# DataControlBoard-Teensy.net
KiCad netlist of a schematic drawn in EAGLE
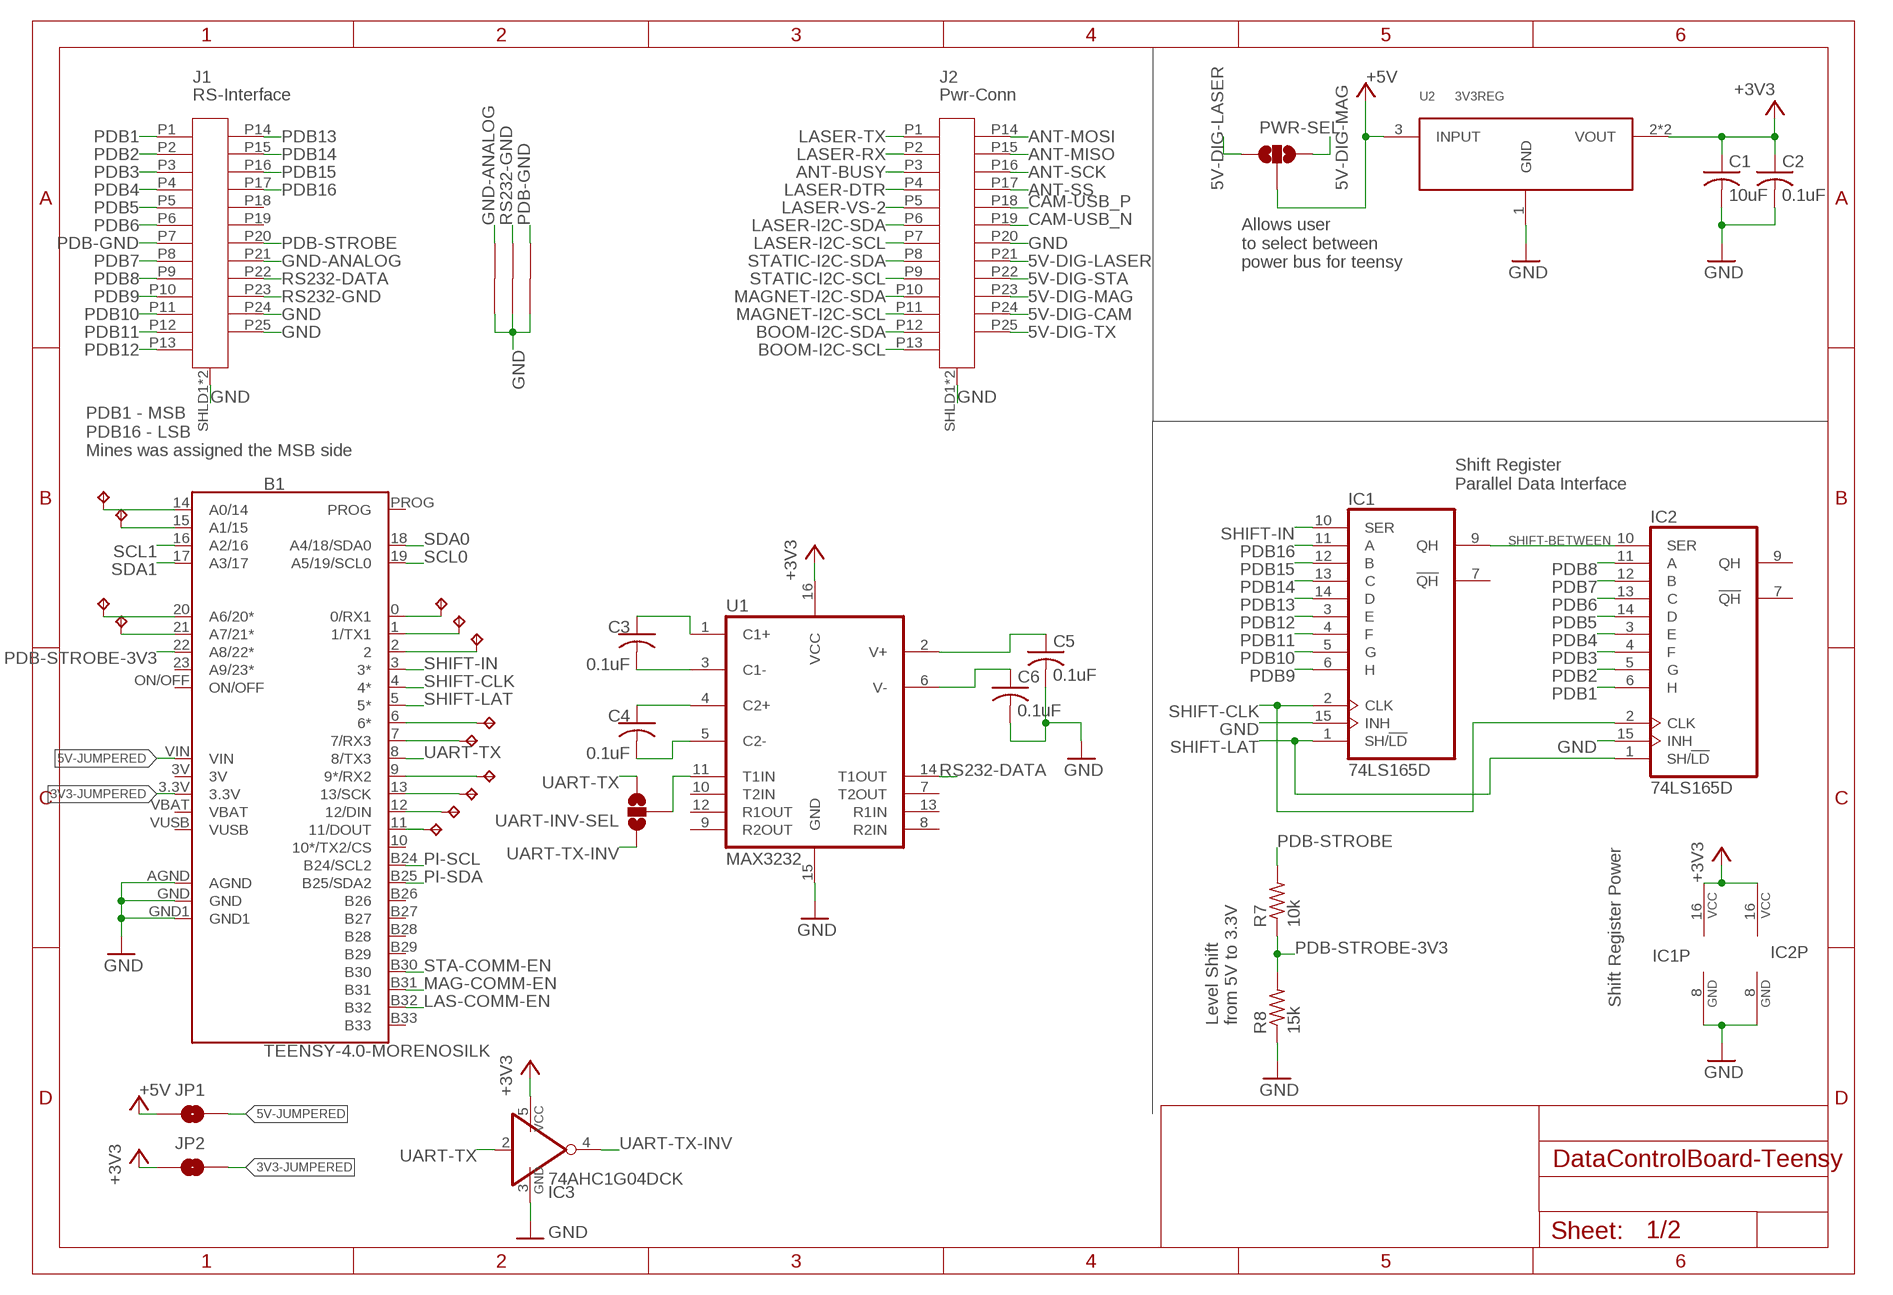
[diagram p0: schematic, sheet 1]
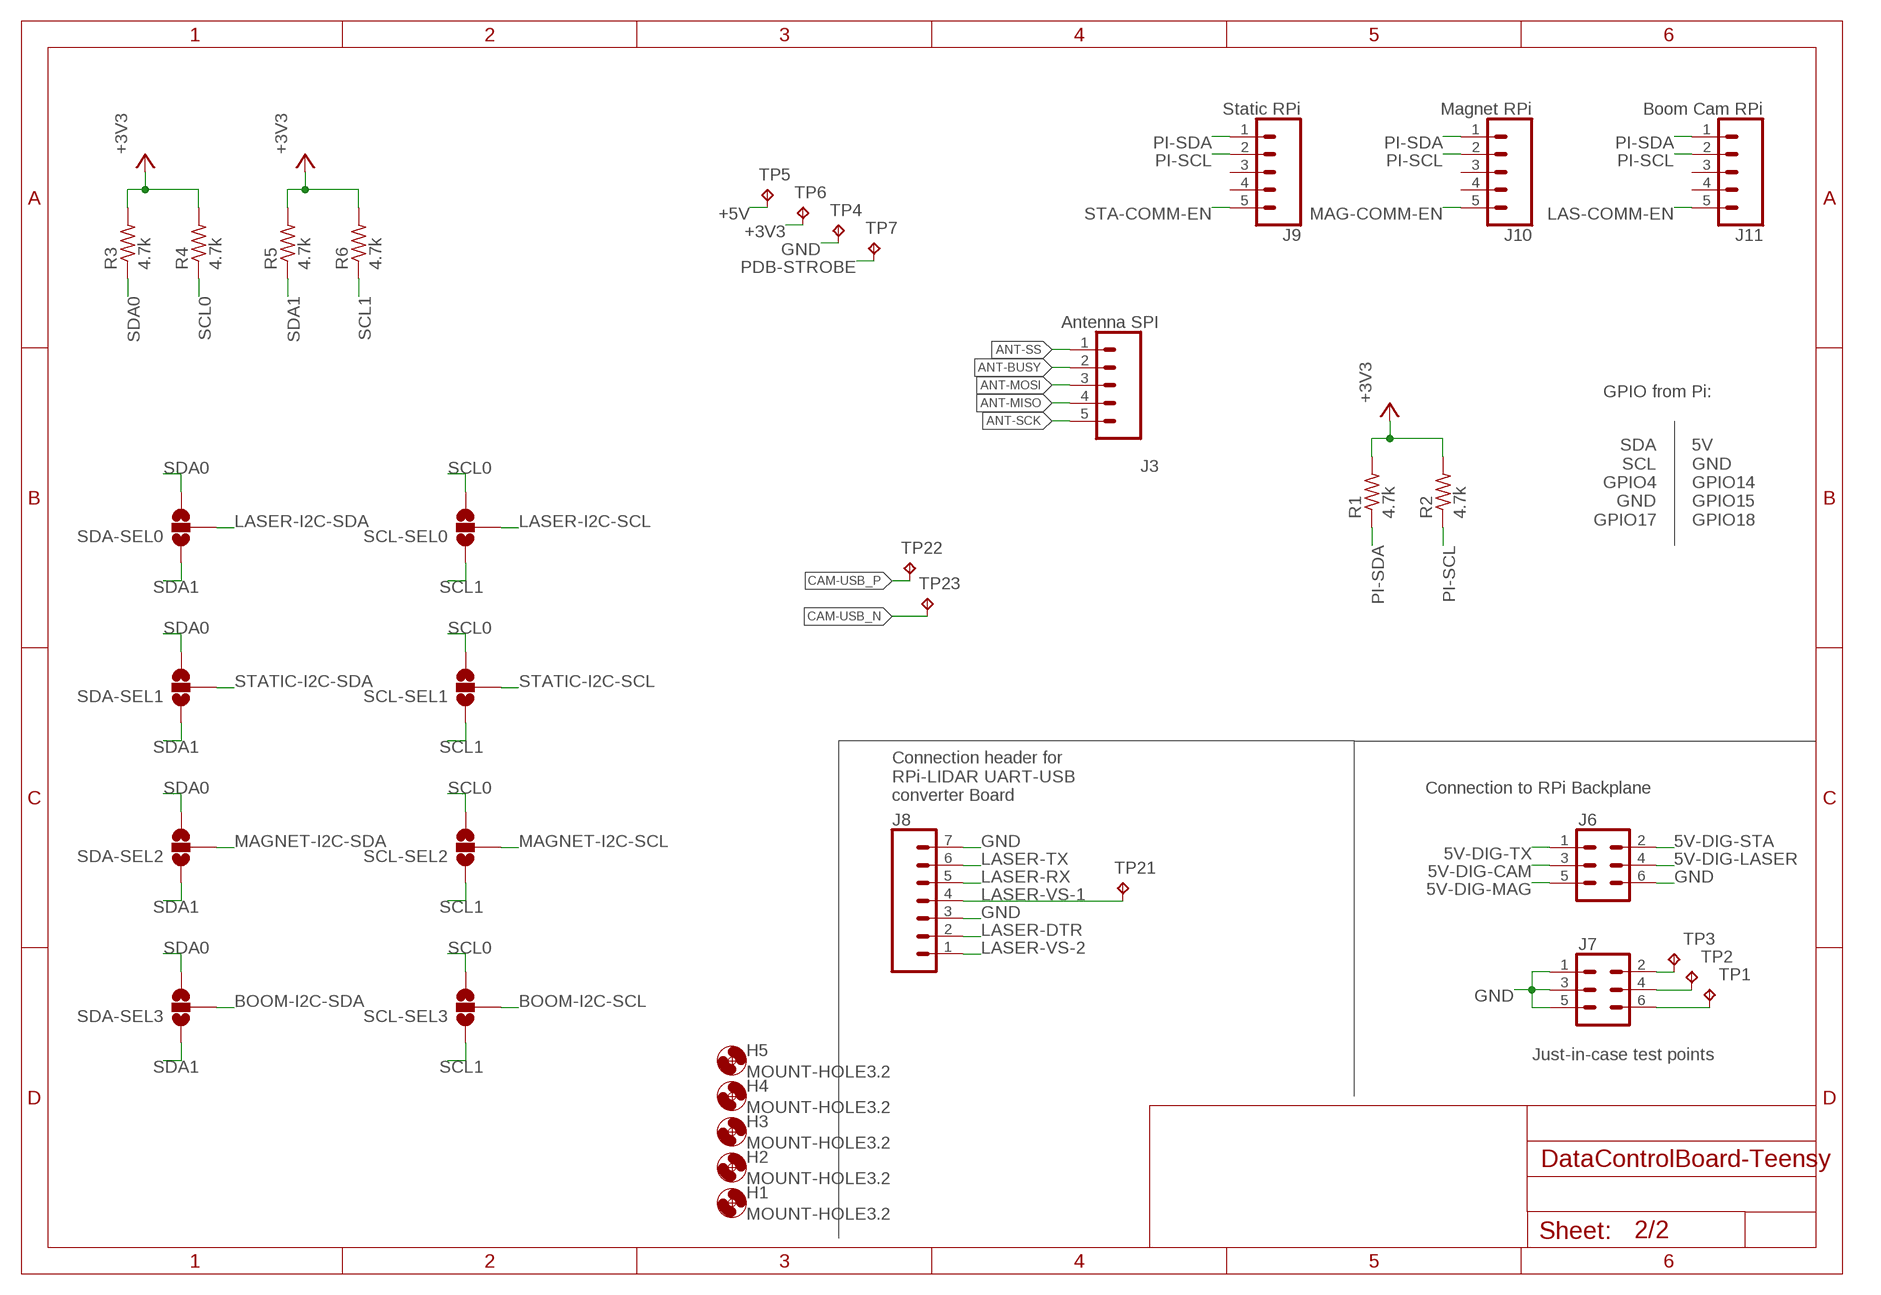
[diagram p1: schematic, sheet 2]

(export (version "E")
  (design (tool "Eeschema 10.0.6"))
  (components
    (comp (ref "B1")
      (value "TEENSY-4.0-MORENOSILK")
      (footprint "eagle-import:TEENSY-4.0_NOSILK")
      (libsource (lib "eagle-import") (part "TEENSY-4.0-MORENOSILK"))
    )
    (comp (ref "C1")
      (value "10uF")
      (footprint "eagle-import:C0805")
      (libsource (lib "eagle-import") (part "C-USC0805"))
    )
    (comp (ref "C2")
      (value "0.1uF")
      (footprint "eagle-import:C0805")
      (libsource (lib "eagle-import") (part "C-USC0805"))
    )
    (comp (ref "C3")
      (value "0.1uF")
      (footprint "eagle-import:C0805")
      (libsource (lib "eagle-import") (part "C-USC0805"))
    )
    (comp (ref "C4")
      (value "0.1uF")
      (footprint "eagle-import:C0805")
      (libsource (lib "eagle-import") (part "C-USC0805"))
    )
    (comp (ref "C5")
      (value "0.1uF")
      (footprint "eagle-import:C0805")
      (libsource (lib "eagle-import") (part "C-USC0805"))
    )
    (comp (ref "C6")
      (value "0.1uF")
      (footprint "eagle-import:C0805")
      (libsource (lib "eagle-import") (part "C-USC0805"))
    )
    (comp (ref "IC1")
      (value "74LS165D")
      (footprint "eagle-import:SO16")
      (libsource (lib "eagle-import") (part "74165DLS"))
    )
    (comp (ref "IC2")
      (value "74LS165D")
      (footprint "eagle-import:SO16")
      (libsource (lib "eagle-import") (part "74165DLS"))
    )
    (comp (ref "IC3")
      (value "74AHC1G04DCK")
      (footprint "eagle-import:SC70-5")
      (libsource (lib "eagle-import") (part "741G04DCKAHC"))
    )
    (comp (ref "J1")
      (value "RS-Interface")
      (footprint "eagle-import:MICRO-D25-RA")
      (libsource (lib "eagle-import") (part "MICRO-D25"))
    )
    (comp (ref "J2")
      (value "Pwr-Conn")
      (footprint "eagle-import:MICRO-D25-RA")
      (libsource (lib "eagle-import") (part "MICRO-D25"))
    )
    (comp (ref "JP1")
      (value "JUMPER-SMT_2_NO_NO-SILK")
      (footprint "eagle-import:SMT-JUMPER_2_NO_NO-SILK")
      (libsource (lib "eagle-import") (part "JUMPER-SMT_2_NO_NO-SILK"))
    )
    (comp (ref "JP2")
      (value "JUMPER-SMT_2_NO_NO-SILK")
      (footprint "eagle-import:SMT-JUMPER_2_NO_NO-SILK")
      (libsource (lib "eagle-import") (part "JUMPER-SMT_2_NO_NO-SILK"))
    )
    (comp (ref "PWR-SEL")
      (value "JUMPER-SMT_3_NO_NO-SILK")
      (footprint "eagle-import:SMT-JUMPER_3_NO_NO-SILK")
      (libsource (lib "eagle-import") (part "JUMPER-SMT_3_NO_NO-SILK"))
    )
    (comp (ref "R7")
      (value "10k")
      (footprint "eagle-import:R0805")
      (libsource (lib "eagle-import") (part "R-US_R0805"))
    )
    (comp (ref "R8")
      (value "15k")
      (footprint "eagle-import:R0805")
      (libsource (lib "eagle-import") (part "R-US_R0805"))
    )
    (comp (ref "TP8")
      (value "TPPAD1-13")
      (footprint "eagle-import:P1-13")
      (libsource (lib "eagle-import") (part "TPPAD1-13"))
    )
    (comp (ref "TP9")
      (value "TPPAD1-13")
      (footprint "eagle-import:P1-13")
      (libsource (lib "eagle-import") (part "TPPAD1-13"))
    )
    (comp (ref "TP10")
      (value "TPPAD1-13")
      (footprint "eagle-import:P1-13")
      (libsource (lib "eagle-import") (part "TPPAD1-13"))
    )
    (comp (ref "TP11")
      (value "TPPAD1-13")
      (footprint "eagle-import:P1-13")
      (libsource (lib "eagle-import") (part "TPPAD1-13"))
    )
    (comp (ref "TP12")
      (value "TPPAD1-13")
      (footprint "eagle-import:P1-13")
      (libsource (lib "eagle-import") (part "TPPAD1-13"))
    )
    (comp (ref "TP13")
      (value "TPPAD1-13")
      (footprint "eagle-import:P1-13")
      (libsource (lib "eagle-import") (part "TPPAD1-13"))
    )
    (comp (ref "TP14")
      (value "TPPAD1-13")
      (footprint "eagle-import:P1-13")
      (libsource (lib "eagle-import") (part "TPPAD1-13"))
    )
    (comp (ref "TP15")
      (value "TPPAD1-13")
      (footprint "eagle-import:P1-13")
      (libsource (lib "eagle-import") (part "TPPAD1-13"))
    )
    (comp (ref "TP16")
      (value "TPPAD1-13")
      (footprint "eagle-import:P1-13")
      (libsource (lib "eagle-import") (part "TPPAD1-13"))
    )
    (comp (ref "TP17")
      (value "TPPAD1-13")
      (footprint "eagle-import:P1-13")
      (libsource (lib "eagle-import") (part "TPPAD1-13"))
    )
    (comp (ref "TP18")
      (value "TPPAD1-13")
      (footprint "eagle-import:P1-13")
      (libsource (lib "eagle-import") (part "TPPAD1-13"))
    )
    (comp (ref "TP19")
      (value "TPPAD1-13")
      (footprint "eagle-import:P1-13")
      (libsource (lib "eagle-import") (part "TPPAD1-13"))
    )
    (comp (ref "TP20")
      (value "TPPAD1-13")
      (footprint "eagle-import:P1-13")
      (libsource (lib "eagle-import") (part "TPPAD1-13"))
    )
    (comp (ref "U$1")
      (value "GND-MERGER")
      (footprint "eagle-import:GND-MERGER")
      (libsource (lib "eagle-import") (part "GND-MERGER"))
    )
    (comp (ref "U$2")
      (value "GND-MERGER")
      (footprint "eagle-import:GND-MERGER")
      (libsource (lib "eagle-import") (part "GND-MERGER"))
    )
    (comp (ref "U$3")
      (value "GND-MERGER")
      (footprint "eagle-import:GND-MERGER")
      (libsource (lib "eagle-import") (part "GND-MERGER"))
    )
    (comp (ref "U1")
      (value "MAX3232")
      (footprint "eagle-import:SO16")
      (libsource (lib "eagle-import") (part "MAX2323SOIC16"))
    )
    (comp (ref "U2")
      (value "3V3REG")
      (footprint "eagle-import:SOT223")
      (libsource (lib "eagle-import") (part "3V3REG"))
    )
    (comp (ref "UART-INV-SEL")
      (value "JUMPER-SMT_3_NO_NO-SILK")
      (footprint "eagle-import:SMT-JUMPER_3_NO_NO-SILK")
      (libsource (lib "eagle-import") (part "JUMPER-SMT_3_NO_NO-SILK"))
    )
    (comp (ref "H1")
      (value "MOUNT-HOLE3.2")
      (footprint "eagle-import:3,2")
      (libsource (lib "eagle-import") (part "MOUNT-HOLE3.2"))
    )
    (comp (ref "H2")
      (value "MOUNT-HOLE3.2")
      (footprint "eagle-import:3,2")
      (libsource (lib "eagle-import") (part "MOUNT-HOLE3.2"))
    )
    (comp (ref "H3")
      (value "MOUNT-HOLE3.2")
      (footprint "eagle-import:3,2")
      (libsource (lib "eagle-import") (part "MOUNT-HOLE3.2"))
    )
    (comp (ref "H4")
      (value "MOUNT-HOLE3.2")
      (footprint "eagle-import:3,2")
      (libsource (lib "eagle-import") (part "MOUNT-HOLE3.2"))
    )
    (comp (ref "H5")
      (value "MOUNT-HOLE3.2")
      (footprint "eagle-import:3,2")
      (libsource (lib "eagle-import") (part "MOUNT-HOLE3.2"))
    )
    (comp (ref "J3")
      (value "Antenna SPI")
      (footprint "eagle-import:1X05_LOCK")
      (libsource (lib "eagle-import") (part "CONN_05LOCK"))
    )
    (comp (ref "J6")
      (value "CONN_03X22X3_SILK_MALE_PTH")
      (footprint "eagle-import:2X3")
      (libsource (lib "eagle-import") (part "CONN_03X22X3_SILK_MALE_PTH"))
    )
    (comp (ref "J7")
      (value "CONN_03X22X3_SILK_MALE_PTH")
      (footprint "eagle-import:2X3")
      (libsource (lib "eagle-import") (part "CONN_03X22X3_SILK_MALE_PTH"))
    )
    (comp (ref "J8")
      (value "CONN_07")
      (footprint "eagle-import:1X07")
      (libsource (lib "eagle-import") (part "CONN_07"))
    )
    (comp (ref "J9")
      (value "Static RPi")
      (footprint "eagle-import:1X05_LOCK")
      (libsource (lib "eagle-import") (part "CONN_05LOCK"))
    )
    (comp (ref "J10")
      (value "Magnet RPi")
      (footprint "eagle-import:1X05_LOCK")
      (libsource (lib "eagle-import") (part "CONN_05LOCK"))
    )
    (comp (ref "J11")
      (value "Boom Cam RPi")
      (footprint "eagle-import:1X05_LOCK")
      (libsource (lib "eagle-import") (part "CONN_05LOCK"))
    )
    (comp (ref "R1")
      (value "4.7k")
      (footprint "eagle-import:R0805")
      (libsource (lib "eagle-import") (part "R-US_R0805"))
    )
    (comp (ref "R2")
      (value "4.7k")
      (footprint "eagle-import:R0805")
      (libsource (lib "eagle-import") (part "R-US_R0805"))
    )
    (comp (ref "R3")
      (value "4.7k")
      (footprint "eagle-import:R0805")
      (libsource (lib "eagle-import") (part "R-US_R0805"))
    )
    (comp (ref "R4")
      (value "4.7k")
      (footprint "eagle-import:R0805")
      (libsource (lib "eagle-import") (part "R-US_R0805"))
    )
    (comp (ref "R5")
      (value "4.7k")
      (footprint "eagle-import:R0805")
      (libsource (lib "eagle-import") (part "R-US_R0805"))
    )
    (comp (ref "R6")
      (value "4.7k")
      (footprint "eagle-import:R0805")
      (libsource (lib "eagle-import") (part "R-US_R0805"))
    )
    (comp (ref "SCL-SEL0")
      (value "JUMPER-SMT_3_NO_NO-SILK")
      (footprint "eagle-import:SMT-JUMPER_3_NO_NO-SILK")
      (libsource (lib "eagle-import") (part "JUMPER-SMT_3_NO_NO-SILK"))
    )
    (comp (ref "SCL-SEL1")
      (value "JUMPER-SMT_3_NO_NO-SILK")
      (footprint "eagle-import:SMT-JUMPER_3_NO_NO-SILK")
      (libsource (lib "eagle-import") (part "JUMPER-SMT_3_NO_NO-SILK"))
    )
    (comp (ref "SCL-SEL2")
      (value "JUMPER-SMT_3_NO_NO-SILK")
      (footprint "eagle-import:SMT-JUMPER_3_NO_NO-SILK")
      (libsource (lib "eagle-import") (part "JUMPER-SMT_3_NO_NO-SILK"))
    )
    (comp (ref "SCL-SEL3")
      (value "JUMPER-SMT_3_NO_NO-SILK")
      (footprint "eagle-import:SMT-JUMPER_3_NO_NO-SILK")
      (libsource (lib "eagle-import") (part "JUMPER-SMT_3_NO_NO-SILK"))
    )
    (comp (ref "SDA-SEL0")
      (value "JUMPER-SMT_3_NO_NO-SILK")
      (footprint "eagle-import:SMT-JUMPER_3_NO_NO-SILK")
      (libsource (lib "eagle-import") (part "JUMPER-SMT_3_NO_NO-SILK"))
    )
    (comp (ref "SDA-SEL1")
      (value "JUMPER-SMT_3_NO_NO-SILK")
      (footprint "eagle-import:SMT-JUMPER_3_NO_NO-SILK")
      (libsource (lib "eagle-import") (part "JUMPER-SMT_3_NO_NO-SILK"))
    )
    (comp (ref "SDA-SEL2")
      (value "JUMPER-SMT_3_NO_NO-SILK")
      (footprint "eagle-import:SMT-JUMPER_3_NO_NO-SILK")
      (libsource (lib "eagle-import") (part "JUMPER-SMT_3_NO_NO-SILK"))
    )
    (comp (ref "SDA-SEL3")
      (value "JUMPER-SMT_3_NO_NO-SILK")
      (footprint "eagle-import:SMT-JUMPER_3_NO_NO-SILK")
      (libsource (lib "eagle-import") (part "JUMPER-SMT_3_NO_NO-SILK"))
    )
    (comp (ref "TP1")
      (value "TPPAD1-13")
      (footprint "eagle-import:P1-13")
      (libsource (lib "eagle-import") (part "TPPAD1-13"))
    )
    (comp (ref "TP2")
      (value "TPPAD1-13")
      (footprint "eagle-import:P1-13")
      (libsource (lib "eagle-import") (part "TPPAD1-13"))
    )
    (comp (ref "TP3")
      (value "TPPAD1-13")
      (footprint "eagle-import:P1-13")
      (libsource (lib "eagle-import") (part "TPPAD1-13"))
    )
    (comp (ref "TP4")
      (value "GND")
      (footprint "eagle-import:P1-13")
      (libsource (lib "eagle-import") (part "TPPAD1-13"))
    )
    (comp (ref "TP5")
      (value "5V")
      (footprint "eagle-import:P1-13")
      (libsource (lib "eagle-import") (part "TPPAD1-13"))
    )
    (comp (ref "TP6")
      (value "3.3V")
      (footprint "eagle-import:P1-13")
      (libsource (lib "eagle-import") (part "TPPAD1-13"))
    )
    (comp (ref "TP7")
      (value "STROBE")
      (footprint "eagle-import:P1-13")
      (libsource (lib "eagle-import") (part "TPPAD1-13"))
    )
    (comp (ref "TP21")
      (value "TPPAD1-13")
      (footprint "eagle-import:P1-13")
      (libsource (lib "eagle-import") (part "TPPAD1-13"))
    )
    (comp (ref "TP22")
      (value "TPPAD1-13")
      (footprint "eagle-import:P1-13")
      (libsource (lib "eagle-import") (part "TPPAD1-13"))
    )
    (comp (ref "TP23")
      (value "TPPAD1-13")
      (footprint "eagle-import:P1-13")
      (libsource (lib "eagle-import") (part "TPPAD1-13"))
    )
  )
  (nets
    (net (code "1") (name "+3V3") (class "Default")
      (node (ref "C1") (pin "1") (pinfunction "1_1") (pintype "passive"))
      (node (ref "C2") (pin "1") (pinfunction "1_1") (pintype "passive"))
      (node (ref "IC1") (pin "16") (pinfunction "VCC_16") (pintype "power_in"))
      (node (ref "IC2") (pin "16") (pinfunction "VCC_16") (pintype "power_in"))
      (node (ref "IC3") (pin "5") (pinfunction "VCC_5") (pintype "power_in"))
      (node (ref "JP2") (pin "1") (pinfunction "1_1") (pintype "passive"))
      (node (ref "R1") (pin "2") (pinfunction "2_2") (pintype "passive"))
      (node (ref "R2") (pin "2") (pinfunction "2_2") (pintype "passive"))
      (node (ref "R3") (pin "2") (pinfunction "2_2") (pintype "passive"))
      (node (ref "R4") (pin "2") (pinfunction "2_2") (pintype "passive"))
      (node (ref "R5") (pin "2") (pinfunction "2_2") (pintype "passive"))
      (node (ref "R6") (pin "2") (pinfunction "2_2") (pintype "passive"))
      (node (ref "TP6") (pin "TP") (pinfunction "TP_TP") (pintype "input"))
      (node (ref "U1") (pin "16") (pinfunction "VCC_16") (pintype "bidirectional"))
      (node (ref "U2") (pin "2") (pinfunction "VOUT_2") (pintype "bidirectional"))
      (node (ref "U2") (pin "4") (pinfunction "VOUT_4") (pintype "bidirectional"))
    )
    (net (code "2") (name "+5V") (class "Default")
      (node (ref "JP1") (pin "1") (pinfunction "1_1") (pintype "passive"))
      (node (ref "PWR-SEL") (pin "2") (pinfunction "2_2") (pintype "passive"))
      (node (ref "TP5") (pin "TP") (pinfunction "TP_TP") (pintype "input"))
      (node (ref "U2") (pin "3") (pinfunction "INPUT_3") (pintype "bidirectional"))
    )
    (net (code "3") (name "3V") (class "Default")
      (node (ref "B1") (pin "3V") (pinfunction "3V_3V") (pintype "power_in"))
    )
    (net (code "4") (name "3V3-JUMPERED") (class "Default")
      (node (ref "B1") (pin "3.3V") (pinfunction "3.3V_3.3V") (pintype "power_in"))
      (node (ref "JP2") (pin "2") (pinfunction "2_2") (pintype "passive"))
    )
    (net (code "5") (name "5V-DIG-CAM") (class "Default")
      (node (ref "J2") (pin "P24") (pinfunction "P24_P24") (pintype "bidirectional"))
      (node (ref "J6") (pin "3") (pinfunction "3_3") (pintype "bidirectional"))
    )
    (net (code "6") (name "5V-DIG-LASER") (class "Default")
      (node (ref "J2") (pin "P21") (pinfunction "P21_P21") (pintype "bidirectional"))
      (node (ref "J6") (pin "4") (pinfunction "4_4") (pintype "bidirectional"))
      (node (ref "PWR-SEL") (pin "1") (pinfunction "1_1") (pintype "passive"))
    )
    (net (code "7") (name "5V-DIG-MAG") (class "Default")
      (node (ref "J2") (pin "P23") (pinfunction "P23_P23") (pintype "bidirectional"))
      (node (ref "J6") (pin "5") (pinfunction "5_5") (pintype "bidirectional"))
      (node (ref "PWR-SEL") (pin "3") (pinfunction "3_3") (pintype "passive"))
    )
    (net (code "8") (name "5V-DIG-STA") (class "Default")
      (node (ref "J2") (pin "P22") (pinfunction "P22_P22") (pintype "bidirectional"))
      (node (ref "J6") (pin "2") (pinfunction "2_2") (pintype "bidirectional"))
    )
    (net (code "9") (name "5V-DIG-TX") (class "Default")
      (node (ref "J2") (pin "P25") (pinfunction "P25_P25") (pintype "bidirectional"))
      (node (ref "J6") (pin "1") (pinfunction "1_1") (pintype "bidirectional"))
    )
    (net (code "10") (name "5V-JUMPERED") (class "Default")
      (node (ref "B1") (pin "VIN") (pinfunction "VIN_VIN") (pintype "power_in"))
      (node (ref "JP1") (pin "2") (pinfunction "2_2") (pintype "passive"))
    )
    (net (code "11") (name "ANT-BUSY") (class "Default")
      (node (ref "J2") (pin "P3") (pinfunction "P3_P3") (pintype "bidirectional"))
      (node (ref "J3") (pin "2") (pinfunction "2_2") (pintype "passive"))
    )
    (net (code "12") (name "ANT-MISO") (class "Default")
      (node (ref "J2") (pin "P15") (pinfunction "P15_P15") (pintype "bidirectional"))
      (node (ref "J3") (pin "4") (pinfunction "4_4") (pintype "passive"))
    )
    (net (code "13") (name "ANT-MOSI") (class "Default")
      (node (ref "J2") (pin "P14") (pinfunction "P14_P14") (pintype "bidirectional"))
      (node (ref "J3") (pin "3") (pinfunction "3_3") (pintype "passive"))
    )
    (net (code "14") (name "ANT-SCK") (class "Default")
      (node (ref "J2") (pin "P16") (pinfunction "P16_P16") (pintype "bidirectional"))
      (node (ref "J3") (pin "5") (pinfunction "5_5") (pintype "passive"))
    )
    (net (code "15") (name "ANT-SS") (class "Default")
      (node (ref "J2") (pin "P17") (pinfunction "P17_P17") (pintype "bidirectional"))
      (node (ref "J3") (pin "1") (pinfunction "1_1") (pintype "passive"))
    )
    (net (code "16") (name "BOOM-I2C-SCL") (class "Default")
      (node (ref "J2") (pin "P13") (pinfunction "P13_P13") (pintype "bidirectional"))
      (node (ref "SCL-SEL3") (pin "2") (pinfunction "2_2") (pintype "passive"))
    )
    (net (code "17") (name "BOOM-I2C-SDA") (class "Default")
      (node (ref "J2") (pin "P12") (pinfunction "P12_P12") (pintype "bidirectional"))
      (node (ref "SDA-SEL3") (pin "2") (pinfunction "2_2") (pintype "passive"))
    )
    (net (code "18") (name "CAM-USB_N") (class "Default")
      (node (ref "J2") (pin "P19") (pinfunction "P19_P19") (pintype "bidirectional"))
      (node (ref "TP23") (pin "TP") (pinfunction "TP_TP") (pintype "input"))
    )
    (net (code "19") (name "CAM-USB_P") (class "Default")
      (node (ref "J2") (pin "P18") (pinfunction "P18_P18") (pintype "bidirectional"))
      (node (ref "TP22") (pin "TP") (pinfunction "TP_TP") (pintype "input"))
    )
    (net (code "20") (name "GND") (class "Default")
      (node (ref "B1") (pin "AGND") (pinfunction "AGND_AGND") (pintype "power_in"))
      (node (ref "B1") (pin "GND") (pinfunction "GND_GND") (pintype "power_in"))
      (node (ref "B1") (pin "GND1") (pinfunction "GND1_GND1") (pintype "power_in"))
      (node (ref "C1") (pin "2") (pinfunction "2_2") (pintype "passive"))
      (node (ref "C2") (pin "2") (pinfunction "2_2") (pintype "passive"))
      (node (ref "C5") (pin "2") (pinfunction "2_2") (pintype "passive"))
      (node (ref "C6") (pin "2") (pinfunction "2_2") (pintype "passive"))
      (node (ref "IC1") (pin "15") (pinfunction "INH_15") (pintype "input"))
      (node (ref "IC1") (pin "8") (pinfunction "GND_8") (pintype "power_in"))
      (node (ref "IC2") (pin "15") (pinfunction "INH_15") (pintype "input"))
      (node (ref "IC2") (pin "8") (pinfunction "GND_8") (pintype "power_in"))
      (node (ref "IC3") (pin "3") (pinfunction "GND_3") (pintype "power_in"))
      (node (ref "J1") (pin "P24") (pinfunction "P24_P24") (pintype "bidirectional"))
      (node (ref "J1") (pin "P25") (pinfunction "P25_P25") (pintype "bidirectional"))
      (node (ref "J1") (pin "SHLD1") (pinfunction "SHLD_SHLD1") (pintype "bidirectional"))
      (node (ref "J1") (pin "SHLD2") (pinfunction "SHLD_SHLD2") (pintype "bidirectional"))
      (node (ref "J2") (pin "P20") (pinfunction "P20_P20") (pintype "bidirectional"))
      (node (ref "J2") (pin "SHLD1") (pinfunction "SHLD_SHLD1") (pintype "bidirectional"))
      (node (ref "J2") (pin "SHLD2") (pinfunction "SHLD_SHLD2") (pintype "bidirectional"))
      (node (ref "J6") (pin "6") (pinfunction "6_6") (pintype "bidirectional"))
      (node (ref "J7") (pin "1") (pinfunction "1_1") (pintype "bidirectional"))
      (node (ref "J7") (pin "3") (pinfunction "3_3") (pintype "bidirectional"))
      (node (ref "J7") (pin "5") (pinfunction "5_5") (pintype "bidirectional"))
      (node (ref "J8") (pin "3") (pinfunction "3_3") (pintype "passive"))
      (node (ref "J8") (pin "7") (pinfunction "7_7") (pintype "passive"))
      (node (ref "R8") (pin "1") (pinfunction "1_1") (pintype "passive"))
      (node (ref "TP4") (pin "TP") (pinfunction "TP_TP") (pintype "input"))
      (node (ref "U$1") (pin "P$1") (pinfunction "P$1_P$1") (pintype "bidirectional"))
      (node (ref "U$2") (pin "P$1") (pinfunction "P$1_P$1") (pintype "bidirectional"))
      (node (ref "U$3") (pin "P$1") (pinfunction "P$1_P$1") (pintype "bidirectional"))
      (node (ref "U1") (pin "15") (pinfunction "GND_15") (pintype "bidirectional"))
      (node (ref "U2") (pin "1") (pinfunction "GND_1") (pintype "bidirectional"))
    )
    (net (code "21") (name "GND-ANALOG") (class "Default")
      (node (ref "J1") (pin "P21") (pinfunction "P21_P21") (pintype "bidirectional"))
      (node (ref "U$1") (pin "P$2") (pinfunction "P$2_P$2") (pintype "bidirectional"))
    )
    (net (code "22") (name "LAS-COMM-EN") (class "Default")
      (node (ref "B1") (pin "B32") (pinfunction "B32_B32") (pintype "bidirectional"))
      (node (ref "J11") (pin "5") (pinfunction "5_5") (pintype "passive"))
    )
    (net (code "23") (name "LASER-DTR") (class "Default")
      (node (ref "J2") (pin "P4") (pinfunction "P4_P4") (pintype "bidirectional"))
      (node (ref "J8") (pin "2") (pinfunction "2_2") (pintype "passive"))
    )
    (net (code "24") (name "LASER-I2C-SCL") (class "Default")
      (node (ref "J2") (pin "P7") (pinfunction "P7_P7") (pintype "bidirectional"))
      (node (ref "SCL-SEL0") (pin "2") (pinfunction "2_2") (pintype "passive"))
    )
    (net (code "25") (name "LASER-I2C-SDA") (class "Default")
      (node (ref "J2") (pin "P6") (pinfunction "P6_P6") (pintype "bidirectional"))
      (node (ref "SDA-SEL0") (pin "2") (pinfunction "2_2") (pintype "passive"))
    )
    (net (code "26") (name "LASER-RX") (class "Default")
      (node (ref "J2") (pin "P2") (pinfunction "P2_P2") (pintype "bidirectional"))
      (node (ref "J8") (pin "5") (pinfunction "5_5") (pintype "passive"))
    )
    (net (code "27") (name "LASER-TX") (class "Default")
      (node (ref "J2") (pin "P1") (pinfunction "P1_P1") (pintype "bidirectional"))
      (node (ref "J8") (pin "6") (pinfunction "6_6") (pintype "passive"))
    )
    (net (code "28") (name "LASER-VS-1") (class "Default")
      (node (ref "J8") (pin "4") (pinfunction "4_4") (pintype "passive"))
      (node (ref "TP21") (pin "TP") (pinfunction "TP_TP") (pintype "input"))
    )
    (net (code "29") (name "LASER-VS-2") (class "Default")
      (node (ref "J2") (pin "P5") (pinfunction "P5_P5") (pintype "bidirectional"))
      (node (ref "J8") (pin "1") (pinfunction "1_1") (pintype "passive"))
    )
    (net (code "30") (name "MAG-COMM-EN") (class "Default")
      (node (ref "B1") (pin "B31") (pinfunction "B31_B31") (pintype "bidirectional"))
      (node (ref "J10") (pin "5") (pinfunction "5_5") (pintype "passive"))
    )
    (net (code "31") (name "MAGNET-I2C-SCL") (class "Default")
      (node (ref "J2") (pin "P11") (pinfunction "P11_P11") (pintype "bidirectional"))
      (node (ref "SCL-SEL2") (pin "2") (pinfunction "2_2") (pintype "passive"))
    )
    (net (code "32") (name "MAGNET-I2C-SDA") (class "Default")
      (node (ref "J2") (pin "P10") (pinfunction "P10_P10") (pintype "bidirectional"))
      (node (ref "SDA-SEL2") (pin "2") (pinfunction "2_2") (pintype "passive"))
    )
    (net (code "33") (name "Net-(B1-0{slash}RX1)") (class "Default")
      (node (ref "B1") (pin "0") (pinfunction "0/RX1_0") (pintype "bidirectional"))
      (node (ref "TP12") (pin "TP") (pinfunction "TP_TP") (pintype "input"))
    )
    (net (code "34") (name "Net-(B1-1{slash}TX1)") (class "Default")
      (node (ref "B1") (pin "1") (pinfunction "1/TX1_1") (pintype "bidirectional"))
      (node (ref "TP13") (pin "TP") (pinfunction "TP_TP") (pintype "input"))
    )
    (net (code "35") (name "Net-(B1-6*)") (class "Default")
      (node (ref "B1") (pin "6") (pinfunction "6*_6") (pintype "bidirectional"))
      (node (ref "TP19") (pin "TP") (pinfunction "TP_TP") (pintype "input"))
    )
    (net (code "36") (name "Net-(B1-7{slash}RX3)") (class "Default")
      (node (ref "B1") (pin "7") (pinfunction "7/RX3_7") (pintype "bidirectional"))
      (node (ref "TP20") (pin "TP") (pinfunction "TP_TP") (pintype "input"))
    )
    (net (code "37") (name "Net-(B1-9*{slash}RX2)") (class "Default")
      (node (ref "B1") (pin "9") (pinfunction "9*/RX2_9") (pintype "bidirectional"))
      (node (ref "TP15") (pin "TP") (pinfunction "TP_TP") (pintype "input"))
    )
    (net (code "38") (name "Net-(B1-11{slash}DOUT)") (class "Default")
      (node (ref "B1") (pin "11") (pinfunction "11/DOUT_11") (pintype "bidirectional"))
      (node (ref "TP18") (pin "TP") (pinfunction "TP_TP") (pintype "input"))
    )
    (net (code "39") (name "Net-(B1-12{slash}DIN)") (class "Default")
      (node (ref "B1") (pin "12") (pinfunction "12/DIN_12") (pintype "bidirectional"))
      (node (ref "TP17") (pin "TP") (pinfunction "TP_TP") (pintype "input"))
    )
    (net (code "40") (name "Net-(B1-13{slash}SCK)") (class "Default")
      (node (ref "B1") (pin "13") (pinfunction "13/SCK_13") (pintype "bidirectional"))
      (node (ref "TP16") (pin "TP") (pinfunction "TP_TP") (pintype "input"))
    )
    (net (code "41") (name "Net-(B1-A0{slash}14)") (class "Default")
      (node (ref "B1") (pin "14") (pinfunction "A0/14_14") (pintype "bidirectional"))
      (node (ref "TP8") (pin "TP") (pinfunction "TP_TP") (pintype "input"))
    )
    (net (code "42") (name "Net-(B1-A1{slash}15)") (class "Default")
      (node (ref "B1") (pin "15") (pinfunction "A1/15_15") (pintype "bidirectional"))
      (node (ref "TP9") (pin "TP") (pinfunction "TP_TP") (pintype "input"))
    )
    (net (code "43") (name "Net-(B1-A6{slash}20*)") (class "Default")
      (node (ref "B1") (pin "20") (pinfunction "A6/20*_20") (pintype "bidirectional"))
      (node (ref "TP10") (pin "TP") (pinfunction "TP_TP") (pintype "input"))
    )
    (net (code "44") (name "Net-(B1-A7{slash}21*)") (class "Default")
      (node (ref "B1") (pin "21") (pinfunction "A7/21*_21") (pintype "bidirectional"))
      (node (ref "TP11") (pin "TP") (pinfunction "TP_TP") (pintype "input"))
    )
    (net (code "45") (name "Net-(B1-Pad2)") (class "Default")
      (node (ref "B1") (pin "2") (pinfunction "2_2") (pintype "bidirectional"))
      (node (ref "TP14") (pin "TP") (pinfunction "TP_TP") (pintype "input"))
    )
    (net (code "46") (name "Net-(J7-Pad2)") (class "Default")
      (node (ref "J7") (pin "2") (pinfunction "2_2") (pintype "bidirectional"))
      (node (ref "TP3") (pin "TP") (pinfunction "TP_TP") (pintype "input"))
    )
    (net (code "47") (name "Net-(J7-Pad4)") (class "Default")
      (node (ref "J7") (pin "4") (pinfunction "4_4") (pintype "bidirectional"))
      (node (ref "TP2") (pin "TP") (pinfunction "TP_TP") (pintype "input"))
    )
    (net (code "48") (name "Net-(J7-Pad6)") (class "Default")
      (node (ref "J7") (pin "6") (pinfunction "6_6") (pintype "bidirectional"))
      (node (ref "TP1") (pin "TP") (pinfunction "TP_TP") (pintype "input"))
    )
    (net (code "49") (name "Net-(U1-C1+)") (class "Default")
      (node (ref "C3") (pin "1") (pinfunction "1_1") (pintype "passive"))
      (node (ref "U1") (pin "1") (pinfunction "C1+_1") (pintype "bidirectional"))
    )
    (net (code "50") (name "Net-(U1-C1-)") (class "Default")
      (node (ref "C3") (pin "2") (pinfunction "2_2") (pintype "passive"))
      (node (ref "U1") (pin "3") (pinfunction "C1-_3") (pintype "bidirectional"))
    )
    (net (code "51") (name "Net-(U1-C2+)") (class "Default")
      (node (ref "C4") (pin "1") (pinfunction "1_1") (pintype "passive"))
      (node (ref "U1") (pin "4") (pinfunction "C2+_4") (pintype "bidirectional"))
    )
    (net (code "52") (name "Net-(U1-C2-)") (class "Default")
      (node (ref "C4") (pin "2") (pinfunction "2_2") (pintype "passive"))
      (node (ref "U1") (pin "5") (pinfunction "C2-_5") (pintype "bidirectional"))
    )
    (net (code "53") (name "Net-(U1-T1IN)") (class "Default")
      (node (ref "U1") (pin "11") (pinfunction "T1IN_11") (pintype "input"))
      (node (ref "UART-INV-SEL") (pin "2") (pinfunction "2_2") (pintype "passive"))
    )
    (net (code "54") (name "Net-(U1-V+)") (class "Default")
      (node (ref "C5") (pin "1") (pinfunction "1_1") (pintype "passive"))
      (node (ref "U1") (pin "2") (pinfunction "V+_2") (pintype "bidirectional"))
    )
    (net (code "55") (name "Net-(U1-V-)") (class "Default")
      (node (ref "C6") (pin "1") (pinfunction "1_1") (pintype "passive"))
      (node (ref "U1") (pin "6") (pinfunction "V-_6") (pintype "bidirectional"))
    )
    (net (code "56") (name "PDB-GND") (class "Default")
      (node (ref "J1") (pin "P7") (pinfunction "P7_P7") (pintype "bidirectional"))
      (node (ref "U$3") (pin "P$2") (pinfunction "P$2_P$2") (pintype "bidirectional"))
    )
    (net (code "57") (name "PDB-STROBE") (class "Default")
      (node (ref "J1") (pin "P20") (pinfunction "P20_P20") (pintype "bidirectional"))
      (node (ref "R7") (pin "2") (pinfunction "2_2") (pintype "passive"))
      (node (ref "TP7") (pin "TP") (pinfunction "TP_TP") (pintype "input"))
    )
    (net (code "58") (name "PDB-STROBE-3V3") (class "Default")
      (node (ref "B1") (pin "22") (pinfunction "A8/22*_22") (pintype "bidirectional"))
      (node (ref "R7") (pin "1") (pinfunction "1_1") (pintype "passive"))
      (node (ref "R8") (pin "2") (pinfunction "2_2") (pintype "passive"))
    )
    (net (code "59") (name "PDB1") (class "Default")
      (node (ref "IC2") (pin "6") (pinfunction "H_6") (pintype "input"))
      (node (ref "J1") (pin "P1") (pinfunction "P1_P1") (pintype "bidirectional"))
    )
    (net (code "60") (name "PDB2") (class "Default")
      (node (ref "IC2") (pin "5") (pinfunction "G_5") (pintype "input"))
      (node (ref "J1") (pin "P2") (pinfunction "P2_P2") (pintype "bidirectional"))
    )
    (net (code "61") (name "PDB3") (class "Default")
      (node (ref "IC2") (pin "4") (pinfunction "F_4") (pintype "input"))
      (node (ref "J1") (pin "P3") (pinfunction "P3_P3") (pintype "bidirectional"))
    )
    (net (code "62") (name "PDB4") (class "Default")
      (node (ref "IC2") (pin "3") (pinfunction "E_3") (pintype "input"))
      (node (ref "J1") (pin "P4") (pinfunction "P4_P4") (pintype "bidirectional"))
    )
    (net (code "63") (name "PDB5") (class "Default")
      (node (ref "IC2") (pin "14") (pinfunction "D_14") (pintype "input"))
      (node (ref "J1") (pin "P5") (pinfunction "P5_P5") (pintype "bidirectional"))
    )
    (net (code "64") (name "PDB6") (class "Default")
      (node (ref "IC2") (pin "13") (pinfunction "C_13") (pintype "input"))
      (node (ref "J1") (pin "P6") (pinfunction "P6_P6") (pintype "bidirectional"))
    )
    (net (code "65") (name "PDB7") (class "Default")
      (node (ref "IC2") (pin "12") (pinfunction "B_12") (pintype "input"))
      (node (ref "J1") (pin "P8") (pinfunction "P8_P8") (pintype "bidirectional"))
    )
    (net (code "66") (name "PDB8") (class "Default")
      (node (ref "IC2") (pin "11") (pinfunction "A_11") (pintype "input"))
      (node (ref "J1") (pin "P9") (pinfunction "P9_P9") (pintype "bidirectional"))
    )
    (net (code "67") (name "PDB9") (class "Default")
      (node (ref "IC1") (pin "6") (pinfunction "H_6") (pintype "input"))
      (node (ref "J1") (pin "P10") (pinfunction "P10_P10") (pintype "bidirectional"))
    )
    (net (code "68") (name "PDB10") (class "Default")
      (node (ref "IC1") (pin "5") (pinfunction "G_5") (pintype "input"))
      (node (ref "J1") (pin "P11") (pinfunction "P11_P11") (pintype "bidirectional"))
    )
    (net (code "69") (name "PDB11") (class "Default")
      (node (ref "IC1") (pin "4") (pinfunction "F_4") (pintype "input"))
      (node (ref "J1") (pin "P12") (pinfunction "P12_P12") (pintype "bidirectional"))
    )
    (net (code "70") (name "PDB12") (class "Default")
      (node (ref "IC1") (pin "3") (pinfunction "E_3") (pintype "input"))
      (node (ref "J1") (pin "P13") (pinfunction "P13_P13") (pintype "bidirectional"))
    )
    (net (code "71") (name "PDB13") (class "Default")
      (node (ref "IC1") (pin "14") (pinfunction "D_14") (pintype "input"))
      (node (ref "J1") (pin "P14") (pinfunction "P14_P14") (pintype "bidirectional"))
    )
    (net (code "72") (name "PDB14") (class "Default")
      (node (ref "IC1") (pin "13") (pinfunction "C_13") (pintype "input"))
      (node (ref "J1") (pin "P15") (pinfunction "P15_P15") (pintype "bidirectional"))
    )
    (net (code "73") (name "PDB15") (class "Default")
      (node (ref "IC1") (pin "12") (pinfunction "B_12") (pintype "input"))
      (node (ref "J1") (pin "P16") (pinfunction "P16_P16") (pintype "bidirectional"))
    )
    (net (code "74") (name "PDB16") (class "Default")
      (node (ref "IC1") (pin "11") (pinfunction "A_11") (pintype "input"))
      (node (ref "J1") (pin "P17") (pinfunction "P17_P17") (pintype "bidirectional"))
    )
    (net (code "75") (name "PI-SCL") (class "Default")
      (node (ref "B1") (pin "B24") (pinfunction "B24/SCL2_B24") (pintype "bidirectional"))
      (node (ref "J10") (pin "2") (pinfunction "2_2") (pintype "passive"))
      (node (ref "J11") (pin "2") (pinfunction "2_2") (pintype "passive"))
      (node (ref "J9") (pin "2") (pinfunction "2_2") (pintype "passive"))
      (node (ref "R2") (pin "1") (pinfunction "1_1") (pintype "passive"))
    )
    (net (code "76") (name "PI-SDA") (class "Default")
      (node (ref "B1") (pin "B25") (pinfunction "B25/SDA2_B25") (pintype "bidirectional"))
      (node (ref "J10") (pin "1") (pinfunction "1_1") (pintype "passive"))
      (node (ref "J11") (pin "1") (pinfunction "1_1") (pintype "passive"))
      (node (ref "J9") (pin "1") (pinfunction "1_1") (pintype "passive"))
      (node (ref "R1") (pin "1") (pinfunction "1_1") (pintype "passive"))
    )
    (net (code "77") (name "RS232-DATA") (class "Default")
      (node (ref "J1") (pin "P22") (pinfunction "P22_P22") (pintype "bidirectional"))
      (node (ref "U1") (pin "14") (pinfunction "T1OUT_14") (pintype "output"))
    )
    (net (code "78") (name "RS232-GND") (class "Default")
      (node (ref "J1") (pin "P23") (pinfunction "P23_P23") (pintype "bidirectional"))
      (node (ref "U$2") (pin "P$2") (pinfunction "P$2_P$2") (pintype "bidirectional"))
    )
    (net (code "79") (name "SCL0") (class "Default")
      (node (ref "B1") (pin "19") (pinfunction "A5/19/SCL0_19") (pintype "bidirectional"))
      (node (ref "R4") (pin "1") (pinfunction "1_1") (pintype "passive"))
      (node (ref "SCL-SEL0") (pin "3") (pinfunction "3_3") (pintype "passive"))
      (node (ref "SCL-SEL1") (pin "3") (pinfunction "3_3") (pintype "passive"))
      (node (ref "SCL-SEL2") (pin "3") (pinfunction "3_3") (pintype "passive"))
      (node (ref "SCL-SEL3") (pin "3") (pinfunction "3_3") (pintype "passive"))
    )
    (net (code "80") (name "SCL1") (class "Default")
      (node (ref "B1") (pin "16") (pinfunction "A2/16_16") (pintype "bidirectional"))
      (node (ref "R6") (pin "1") (pinfunction "1_1") (pintype "passive"))
      (node (ref "SCL-SEL0") (pin "1") (pinfunction "1_1") (pintype "passive"))
      (node (ref "SCL-SEL1") (pin "1") (pinfunction "1_1") (pintype "passive"))
      (node (ref "SCL-SEL2") (pin "1") (pinfunction "1_1") (pintype "passive"))
      (node (ref "SCL-SEL3") (pin "1") (pinfunction "1_1") (pintype "passive"))
    )
    (net (code "81") (name "SDA0") (class "Default")
      (node (ref "B1") (pin "18") (pinfunction "A4/18/SDA0_18") (pintype "bidirectional"))
      (node (ref "R3") (pin "1") (pinfunction "1_1") (pintype "passive"))
      (node (ref "SDA-SEL0") (pin "3") (pinfunction "3_3") (pintype "passive"))
      (node (ref "SDA-SEL1") (pin "3") (pinfunction "3_3") (pintype "passive"))
      (node (ref "SDA-SEL2") (pin "3") (pinfunction "3_3") (pintype "passive"))
      (node (ref "SDA-SEL3") (pin "3") (pinfunction "3_3") (pintype "passive"))
    )
    (net (code "82") (name "SDA1") (class "Default")
      (node (ref "B1") (pin "17") (pinfunction "A3/17_17") (pintype "bidirectional"))
      (node (ref "R5") (pin "1") (pinfunction "1_1") (pintype "passive"))
      (node (ref "SDA-SEL0") (pin "1") (pinfunction "1_1") (pintype "passive"))
      (node (ref "SDA-SEL1") (pin "1") (pinfunction "1_1") (pintype "passive"))
      (node (ref "SDA-SEL2") (pin "1") (pinfunction "1_1") (pintype "passive"))
      (node (ref "SDA-SEL3") (pin "1") (pinfunction "1_1") (pintype "passive"))
    )
    (net (code "83") (name "SHIFT-BETWEEN") (class "Default")
      (node (ref "IC1") (pin "9") (pinfunction "QH_9") (pintype "output"))
      (node (ref "IC2") (pin "10") (pinfunction "SER_10") (pintype "input"))
    )
    (net (code "84") (name "SHIFT-CLK") (class "Default")
      (node (ref "B1") (pin "4") (pinfunction "4*_4") (pintype "bidirectional"))
      (node (ref "IC1") (pin "2") (pinfunction "CLK_2") (pintype "input"))
      (node (ref "IC2") (pin "2") (pinfunction "CLK_2") (pintype "input"))
    )
    (net (code "85") (name "SHIFT-IN") (class "Default")
      (node (ref "B1") (pin "3") (pinfunction "3*_3") (pintype "bidirectional"))
      (node (ref "IC1") (pin "10") (pinfunction "SER_10") (pintype "input"))
    )
    (net (code "86") (name "SHIFT-LAT") (class "Default")
      (node (ref "B1") (pin "5") (pinfunction "5*_5") (pintype "bidirectional"))
      (node (ref "IC1") (pin "1") (pinfunction "SH/~{LD}_1") (pintype "input"))
      (node (ref "IC2") (pin "1") (pinfunction "SH/~{LD}_1") (pintype "input"))
    )
    (net (code "87") (name "STA-COMM-EN") (class "Default")
      (node (ref "B1") (pin "B30") (pinfunction "B30_B30") (pintype "bidirectional"))
      (node (ref "J9") (pin "5") (pinfunction "5_5") (pintype "passive"))
    )
    (net (code "88") (name "STATIC-I2C-SCL") (class "Default")
      (node (ref "J2") (pin "P9") (pinfunction "P9_P9") (pintype "bidirectional"))
      (node (ref "SCL-SEL1") (pin "2") (pinfunction "2_2") (pintype "passive"))
    )
    (net (code "89") (name "STATIC-I2C-SDA") (class "Default")
      (node (ref "J2") (pin "P8") (pinfunction "P8_P8") (pintype "bidirectional"))
      (node (ref "SDA-SEL1") (pin "2") (pinfunction "2_2") (pintype "passive"))
    )
    (net (code "90") (name "UART-TX") (class "Default")
      (node (ref "B1") (pin "8") (pinfunction "8/TX3_8") (pintype "bidirectional"))
      (node (ref "IC3") (pin "2") (pinfunction "I_2") (pintype "input"))
      (node (ref "UART-INV-SEL") (pin "3") (pinfunction "3_3") (pintype "passive"))
    )
    (net (code "91") (name "UART-TX-INV") (class "Default")
      (node (ref "IC3") (pin "4") (pinfunction "O_4") (pintype "output"))
      (node (ref "UART-INV-SEL") (pin "1") (pinfunction "1_1") (pintype "passive"))
    )
    (net (code "92") (name "VBAT") (class "Default")
      (node (ref "B1") (pin "VBAT") (pinfunction "VBAT_VBAT") (pintype "power_in"))
    )
    (net (code "93") (name "VUSB") (class "Default")
      (node (ref "B1") (pin "VUSB") (pinfunction "VUSB_VUSB") (pintype "power_in"))
    )
    (net (code "94") (name "unconnected-(B1-10*{slash}TX2{slash}CS-Pad10)") (class "Default")
      (node (ref "B1") (pin "10") (pinfunction "10*/TX2/CS_10") (pintype "bidirectional"))
    )
    (net (code "95") (name "unconnected-(B1-A9{slash}23*-Pad23)") (class "Default")
      (node (ref "B1") (pin "23") (pinfunction "A9/23*_23") (pintype "bidirectional"))
    )
    (net (code "96") (name "unconnected-(B1-PadB26)") (class "Default")
      (node (ref "B1") (pin "B26") (pinfunction "B26_B26") (pintype "bidirectional"))
    )
    (net (code "97") (name "unconnected-(B1-PadB27)") (class "Default")
      (node (ref "B1") (pin "B27") (pinfunction "B27_B27") (pintype "bidirectional"))
    )
    (net (code "98") (name "unconnected-(B1-PadB28)") (class "Default")
      (node (ref "B1") (pin "B28") (pinfunction "B28_B28") (pintype "bidirectional"))
    )
    (net (code "99") (name "unconnected-(B1-PadB29)") (class "Default")
      (node (ref "B1") (pin "B29") (pinfunction "B29_B29") (pintype "bidirectional"))
    )
    (net (code "100") (name "unconnected-(B1-PadB33)") (class "Default")
      (node (ref "B1") (pin "B33") (pinfunction "B33_B33") (pintype "bidirectional"))
    )
    (net (code "101") (name "unconnected-(B1-PadON{slash}OFF)") (class "Default")
      (node (ref "B1") (pin "ON/OFF") (pinfunction "ON/OFF_ON/OFF") (pintype "bidirectional"))
    )
    (net (code "102") (name "unconnected-(B1-PadPROG)") (class "Default")
      (node (ref "B1") (pin "PROG") (pinfunction "PROG_PROG") (pintype "bidirectional"))
    )
    (net (code "103") (name "unconnected-(IC1A-~{QH}-Pad7)") (class "Default")
      (node (ref "IC1") (pin "7") (pinfunction "~{QH}_7") (pintype "output"))
    )
    (net (code "104") (name "unconnected-(IC2A-QH-Pad9)") (class "Default")
      (node (ref "IC2") (pin "9") (pinfunction "QH_9") (pintype "output"))
    )
    (net (code "105") (name "unconnected-(IC2A-~{QH}-Pad7)") (class "Default")
      (node (ref "IC2") (pin "7") (pinfunction "~{QH}_7") (pintype "output"))
    )
    (net (code "106") (name "unconnected-(J1-PadP18)") (class "Default")
      (node (ref "J1") (pin "P18") (pinfunction "P18_P18") (pintype "bidirectional"))
    )
    (net (code "107") (name "unconnected-(J1-PadP19)") (class "Default")
      (node (ref "J1") (pin "P19") (pinfunction "P19_P19") (pintype "bidirectional"))
    )
    (net (code "108") (name "unconnected-(J9-Pad3)") (class "Default")
      (node (ref "J9") (pin "3") (pinfunction "3_3") (pintype "passive"))
    )
    (net (code "109") (name "unconnected-(J9-Pad4)") (class "Default")
      (node (ref "J9") (pin "4") (pinfunction "4_4") (pintype "passive"))
    )
    (net (code "110") (name "unconnected-(J10-Pad3)") (class "Default")
      (node (ref "J10") (pin "3") (pinfunction "3_3") (pintype "passive"))
    )
    (net (code "111") (name "unconnected-(J10-Pad4)") (class "Default")
      (node (ref "J10") (pin "4") (pinfunction "4_4") (pintype "passive"))
    )
    (net (code "112") (name "unconnected-(J11-Pad3)") (class "Default")
      (node (ref "J11") (pin "3") (pinfunction "3_3") (pintype "passive"))
    )
    (net (code "113") (name "unconnected-(J11-Pad4)") (class "Default")
      (node (ref "J11") (pin "4") (pinfunction "4_4") (pintype "passive"))
    )
    (net (code "114") (name "unconnected-(U1-R1IN-Pad13)") (class "Default")
      (node (ref "U1") (pin "13") (pinfunction "R1IN_13") (pintype "input"))
    )
    (net (code "115") (name "unconnected-(U1-R1OUT-Pad12)") (class "Default")
      (node (ref "U1") (pin "12") (pinfunction "R1OUT_12") (pintype "output"))
    )
    (net (code "116") (name "unconnected-(U1-R2IN-Pad8)") (class "Default")
      (node (ref "U1") (pin "8") (pinfunction "R2IN_8") (pintype "input"))
    )
    (net (code "117") (name "unconnected-(U1-R2OUT-Pad9)") (class "Default")
      (node (ref "U1") (pin "9") (pinfunction "R2OUT_9") (pintype "output"))
    )
    (net (code "118") (name "unconnected-(U1-T2IN-Pad10)") (class "Default")
      (node (ref "U1") (pin "10") (pinfunction "T2IN_10") (pintype "input"))
    )
    (net (code "119") (name "unconnected-(U1-T2OUT-Pad7)") (class "Default")
      (node (ref "U1") (pin "7") (pinfunction "T2OUT_7") (pintype "output"))
    )
  )
)
